# relay_matrix.net
KiCad netlist of a schematic drawn in Altium Designer
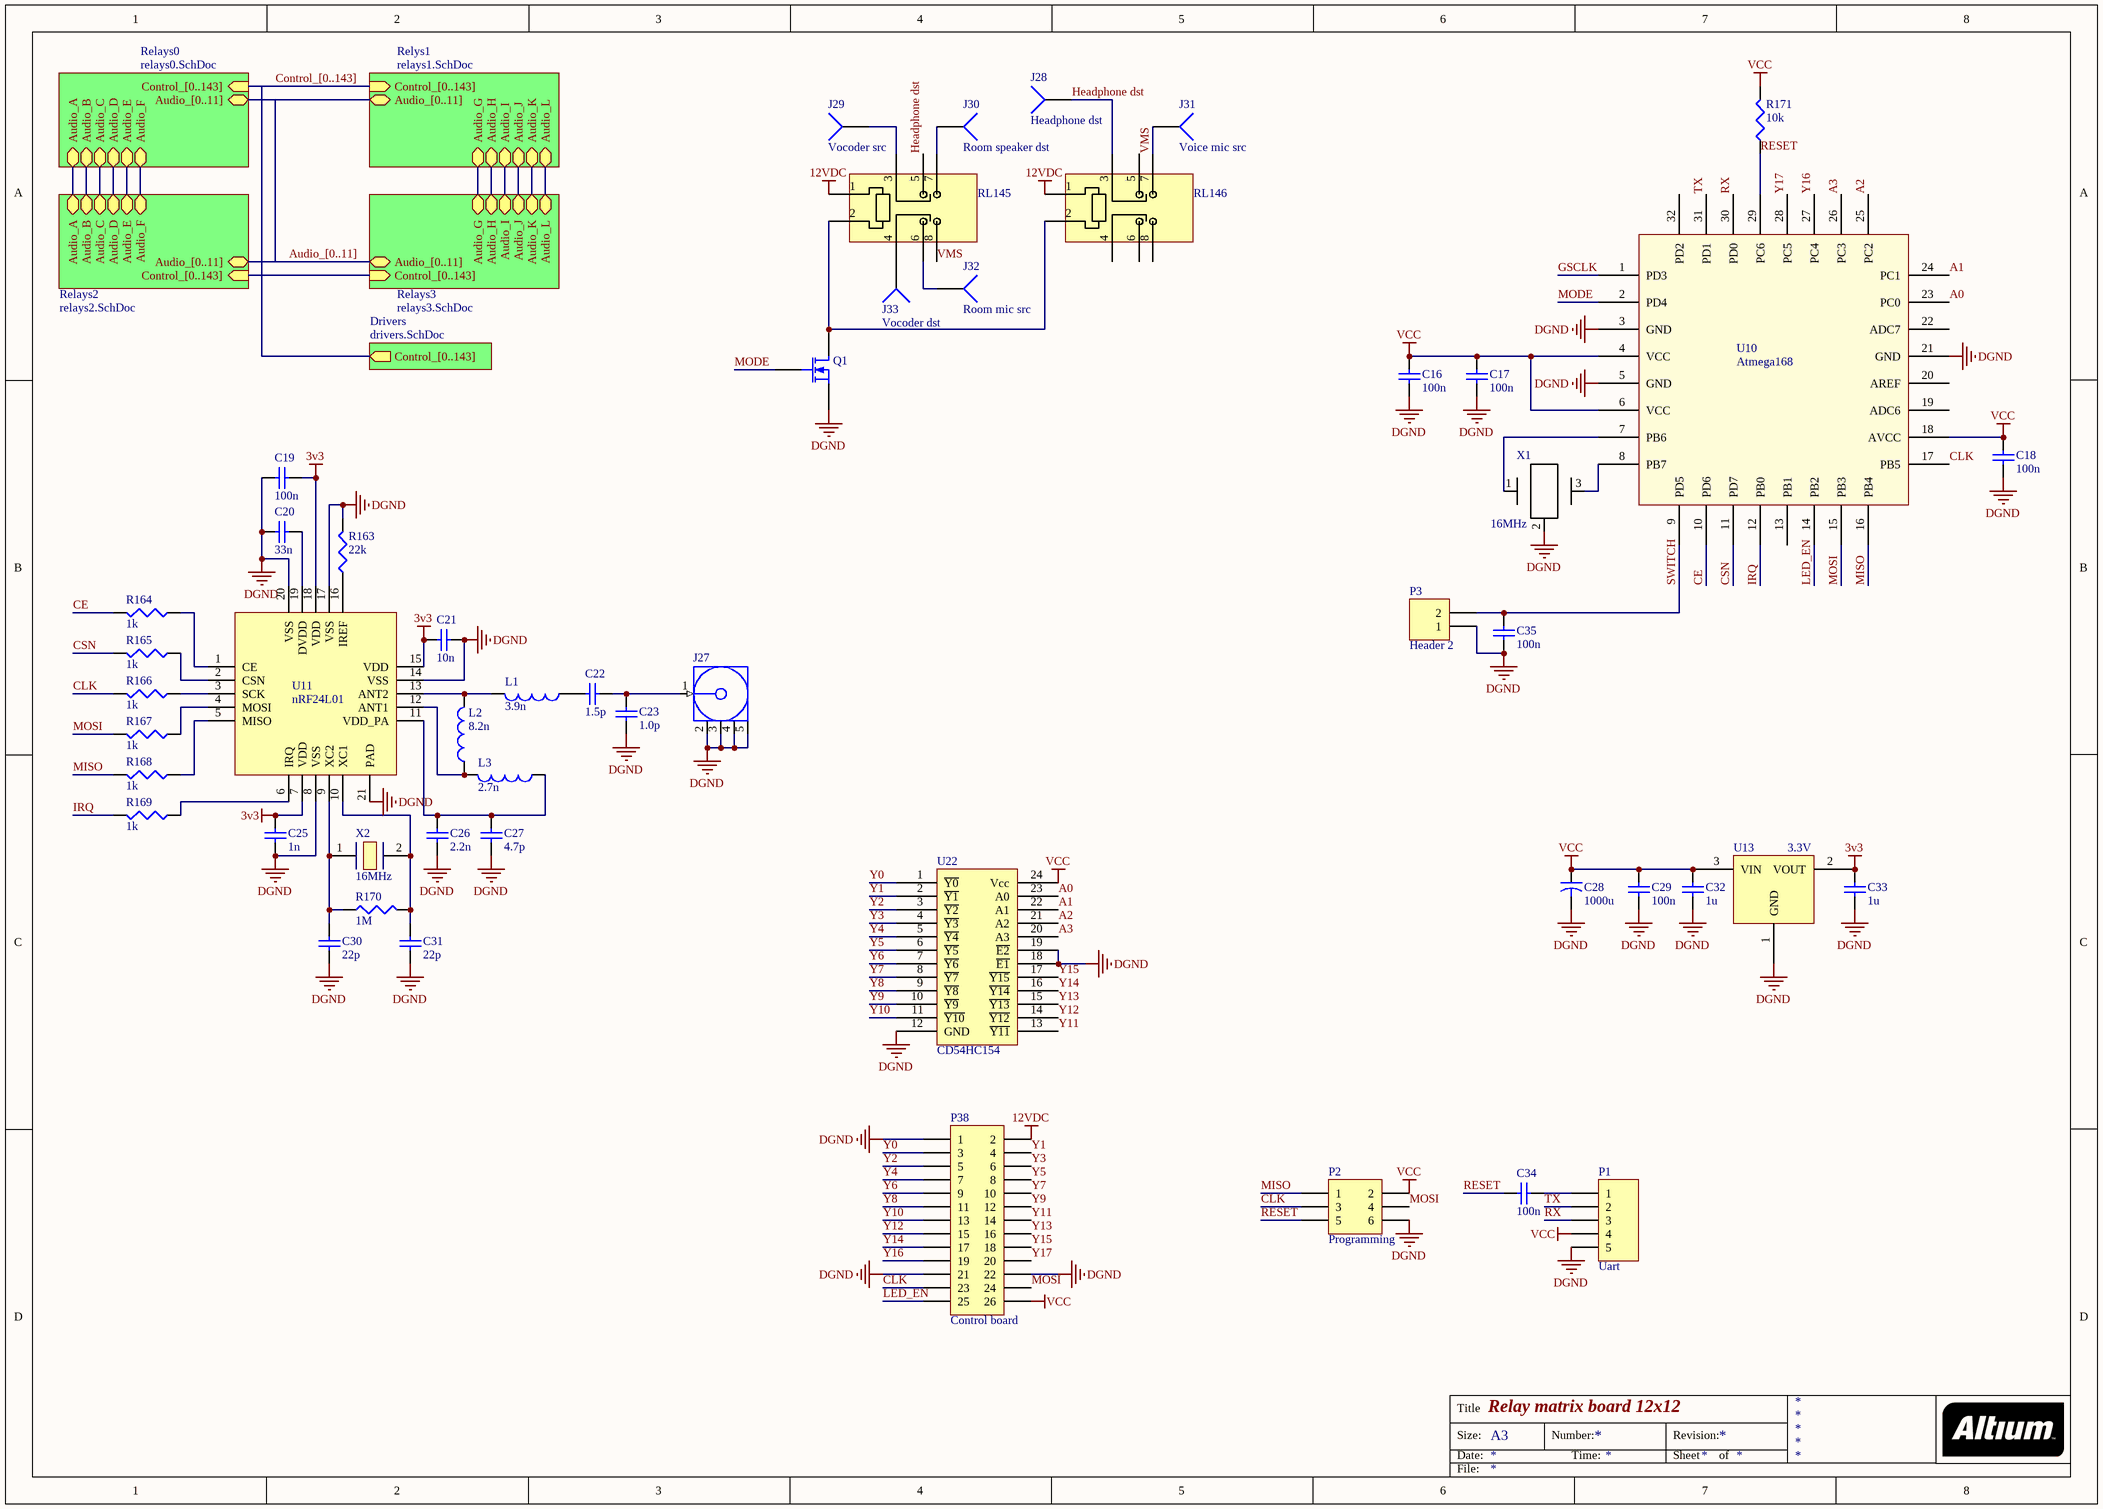
[diagram p0: relay_matrix.SchDoc]

(export (version "E")
  (design (tool "Eeschema 10.0.6"))
  (components
    (comp (ref "C16")
      (value "100n")
      (footprint "1608[0603]")
      (description "Capacitor (Semiconductor SIM Model)")
      (fields (field (name "Comment") "Cap Semi") (field (name "PUBLISHER") "Altium Limited"))
      (libsource (lib "Miscellaneous Devices") (part "Cap Semi"))
    )
    (comp (ref "C17")
      (value "100n")
      (footprint "1608[0603]")
      (description "Capacitor (Semiconductor SIM Model)")
      (fields (field (name "Comment") "Cap Semi") (field (name "PUBLISHER") "Altium Limited"))
      (libsource (lib "Miscellaneous Devices") (part "Cap Semi"))
    )
    (comp (ref "C18")
      (value "100n")
      (footprint "1608[0603]")
      (description "Capacitor (Semiconductor SIM Model)")
      (fields (field (name "Comment") "Cap Semi") (field (name "PUBLISHER") "Altium Limited"))
      (libsource (lib "Miscellaneous Devices") (part "Cap Semi"))
    )
    (comp (ref "C19")
      (value "100n")
      (footprint "1608[0603]")
      (description "Capacitor (Semiconductor SIM Model)")
      (fields (field (name "Comment") "Cap Semi") (field (name "PUBLISHER") "Altium Limited"))
      (libsource (lib "Miscellaneous Devices") (part "Cap Semi"))
    )
    (comp (ref "C20")
      (value "33n")
      (footprint "1608[0603]")
      (description "Capacitor (Semiconductor SIM Model)")
      (fields (field (name "Comment") "Cap Semi") (field (name "PUBLISHER") "Altium Limited"))
      (libsource (lib "Miscellaneous Devices") (part "Cap Semi"))
    )
    (comp (ref "C21")
      (value "10n")
      (footprint "1608[0603]")
      (description "Capacitor (Semiconductor SIM Model)")
      (fields (field (name "Comment") "Cap Semi") (field (name "PUBLISHER") "Altium Limited"))
      (libsource (lib "Miscellaneous Devices") (part "Cap Semi"))
    )
    (comp (ref "C22")
      (value "1.5p")
      (footprint "1608[0603]")
      (description "Capacitor (Semiconductor SIM Model)")
      (fields (field (name "Comment") "Cap Semi") (field (name "PUBLISHER") "Altium Limited"))
      (libsource (lib "Miscellaneous Devices") (part "Cap Semi"))
    )
    (comp (ref "C23")
      (value "1.0p")
      (footprint "1608[0603]")
      (description "Capacitor (Semiconductor SIM Model)")
      (fields (field (name "Comment") "Cap Semi") (field (name "PUBLISHER") "Altium Limited"))
      (libsource (lib "Miscellaneous Devices") (part "Cap Semi"))
    )
    (comp (ref "C25")
      (value "1n")
      (footprint "1608[0603]")
      (description "Capacitor (Semiconductor SIM Model)")
      (fields (field (name "Comment") "Cap Semi") (field (name "PUBLISHER") "Altium Limited"))
      (libsource (lib "Miscellaneous Devices") (part "Cap Semi"))
    )
    (comp (ref "C26")
      (value "2.2n")
      (footprint "1608[0603]")
      (description "Capacitor (Semiconductor SIM Model)")
      (fields (field (name "Comment") "Cap Semi") (field (name "PUBLISHER") "Altium Limited"))
      (libsource (lib "Miscellaneous Devices") (part "Cap Semi"))
    )
    (comp (ref "C27")
      (value "4.7p")
      (footprint "1608[0603]")
      (description "Capacitor (Semiconductor SIM Model)")
      (fields (field (name "Comment") "Cap Semi") (field (name "PUBLISHER") "Altium Limited"))
      (libsource (lib "Miscellaneous Devices") (part "Cap Semi"))
    )
    (comp (ref "C28")
      (value "1000u")
      (footprint "Cap_10x16mm")
      (description "Capacitor")
      (fields (field (name "Comment") "Cap2") (field (name "PUBLISHER") "Altium Limited"))
      (libsource (lib "Miscellaneous Devices") (part "Cap2"))
    )
    (comp (ref "C29")
      (value "100n")
      (footprint "1608[0603]")
      (description "Capacitor (Semiconductor SIM Model)")
      (fields (field (name "Comment") "Cap Semi") (field (name "PUBLISHER") "Altium Limited"))
      (libsource (lib "Miscellaneous Devices") (part "Cap Semi"))
    )
    (comp (ref "C30")
      (value "22p")
      (footprint "1608[0603]")
      (description "Capacitor (Semiconductor SIM Model)")
      (fields (field (name "Comment") "Cap Semi") (field (name "PUBLISHER") "Altium Limited"))
      (libsource (lib "Miscellaneous Devices") (part "Cap Semi"))
    )
    (comp (ref "C31")
      (value "22p")
      (footprint "1608[0603]")
      (description "Capacitor (Semiconductor SIM Model)")
      (fields (field (name "Comment") "Cap Semi") (field (name "PUBLISHER") "Altium Limited"))
      (libsource (lib "Miscellaneous Devices") (part "Cap Semi"))
    )
    (comp (ref "C32")
      (value "1u")
      (footprint "1608[0603]")
      (description "Capacitor (Semiconductor SIM Model)")
      (fields (field (name "Comment") "Cap Semi") (field (name "PUBLISHER") "Altium Limited"))
      (libsource (lib "Miscellaneous Devices") (part "Cap Semi"))
    )
    (comp (ref "C33")
      (value "1u")
      (footprint "1608[0603]")
      (description "Capacitor (Semiconductor SIM Model)")
      (fields (field (name "Comment") "Cap Semi") (field (name "PUBLISHER") "Altium Limited"))
      (libsource (lib "Miscellaneous Devices") (part "Cap Semi"))
    )
    (comp (ref "C34")
      (value "100n")
      (footprint "1608[0603]")
      (description "Capacitor (Semiconductor SIM Model)")
      (fields (field (name "Comment") "Cap Semi") (field (name "PUBLISHER") "Altium Limited"))
      (libsource (lib "Miscellaneous Devices") (part "Cap Semi"))
    )
    (comp (ref "C35")
      (value "100n")
      (footprint "1608[0603]")
      (description "Capacitor (Semiconductor SIM Model)")
      (fields (field (name "Comment") "Cap Semi") (field (name "PUBLISHER") "Altium Limited"))
      (libsource (lib "Miscellaneous Devices") (part "Cap Semi"))
    )
    (comp (ref "J27")
      (value "COAX-F")
      (footprint "MCX5.08-H5")
      (fields (field (name "PUBLISHER") "Altium Limited"))
      (libsource (lib "Miscellaneous Connectors") (part "COAX-F"))
    )
    (comp (ref "J28")
      (value "Headphone dst")
      (footprint "Conn_1_2x4")
      (description "Socket")
      (fields (field (name "PUBLISHER") "Altium Limited"))
      (libsource (lib "Miscellaneous Connectors") (part "Socket"))
    )
    (comp (ref "J29")
      (value "Vocoder src")
      (footprint "Conn_1_2x4")
      (description "Socket")
      (fields (field (name "PUBLISHER") "Altium Limited"))
      (libsource (lib "Miscellaneous Connectors") (part "Socket"))
    )
    (comp (ref "J30")
      (value "Room speaker dst")
      (footprint "Conn_1_2x4")
      (description "Socket")
      (fields (field (name "PUBLISHER") "Altium Limited"))
      (libsource (lib "Miscellaneous Connectors") (part "Socket"))
    )
    (comp (ref "J31")
      (value "Voice mic src")
      (footprint "Conn_1_2x4")
      (description "Socket")
      (fields (field (name "PUBLISHER") "Altium Limited"))
      (libsource (lib "Miscellaneous Connectors") (part "Socket"))
    )
    (comp (ref "J32")
      (value "Room mic src")
      (footprint "Conn_1_2x4")
      (description "Socket")
      (fields (field (name "PUBLISHER") "Altium Limited"))
      (libsource (lib "Miscellaneous Connectors") (part "Socket"))
    )
    (comp (ref "J33")
      (value "Vocoder dst")
      (footprint "Conn_1_2x4")
      (description "Socket")
      (fields (field (name "PUBLISHER") "Altium Limited"))
      (libsource (lib "Miscellaneous Connectors") (part "Socket"))
    )
    (comp (ref "L1")
      (value "3.9n")
      (footprint "1608[0603]")
      (description "Inductor")
      (fields (field (name "PUBLISHER") "Altium Limited"))
      (libsource (lib "Miscellaneous Devices") (part "Inductor"))
    )
    (comp (ref "L2")
      (value "8.2n")
      (footprint "1608[0603]")
      (description "Inductor")
      (fields (field (name "PUBLISHER") "Altium Limited"))
      (libsource (lib "Miscellaneous Devices") (part "Inductor"))
    )
    (comp (ref "L3")
      (value "2.7n")
      (footprint "1608[0603]")
      (description "Inductor")
      (fields (field (name "PUBLISHER") "Altium Limited"))
      (libsource (lib "Miscellaneous Devices") (part "Inductor"))
    )
    (comp (ref "P1")
      (value "Uart")
      (footprint "HDR1X5")
      (description "Header, 5-Pin")
      (fields (field (name "PUBLISHER") "Altium Limited"))
      (libsource (lib "Miscellaneous Connectors") (part "Header 5"))
    )
    (comp (ref "P2")
      (value "Programming")
      (footprint "HDR2X3H")
      (description "Header, 3-Pin, Dual row, Right Angle")
      (fields (field (name "PUBLISHER") "Altium Limited"))
      (libsource (lib "Miscellaneous Connectors") (part "Header 3X2H"))
    )
    (comp (ref "P3")
      (value "Header 2")
      (footprint "HDR1X2")
      (description "Header, 2-Pin")
      (fields (field (name "PUBLISHER") "Altium Limited"))
      (libsource (lib "Miscellaneous Connectors") (part "Header 2"))
    )
    (comp (ref "P38")
      (value "Control board")
      (footprint "HDR2X13")
      (description "Header, 13-Pin, Dual row")
      (fields (field (name "PUBLISHER") "Altium Limited"))
      (libsource (lib "Miscellaneous Connectors") (part "Header 13X2"))
    )
    (comp (ref "Q1")
      (value "MOSFET-N")
      (footprint "SOT23_M")
      (description "N-Channel MOSFET")
      (fields (field (name "PUBLISHER") "Altium Limited"))
      (libsource (lib "Miscellaneous Devices") (part "MOSFET-N"))
    )
    (comp (ref "R163")
      (value "22k")
      (footprint "J1-0603")
      (description "Resistor")
      (fields (field (name "Comment") "Res3") (field (name "PUBLISHER") "Altium Limited"))
      (libsource (lib "Miscellaneous Devices") (part "Res3"))
    )
    (comp (ref "R164")
      (value "1k")
      (footprint "J1-0603")
      (description "Resistor")
      (fields (field (name "Comment") "Res3") (field (name "PUBLISHER") "Altium Limited"))
      (libsource (lib "Miscellaneous Devices") (part "Res3"))
    )
    (comp (ref "R165")
      (value "1k")
      (footprint "J1-0603")
      (description "Resistor")
      (fields (field (name "Comment") "Res3") (field (name "PUBLISHER") "Altium Limited"))
      (libsource (lib "Miscellaneous Devices") (part "Res3"))
    )
    (comp (ref "R166")
      (value "1k")
      (footprint "J1-0603")
      (description "Resistor")
      (fields (field (name "Comment") "Res3") (field (name "PUBLISHER") "Altium Limited"))
      (libsource (lib "Miscellaneous Devices") (part "Res3"))
    )
    (comp (ref "R167")
      (value "1k")
      (footprint "J1-0603")
      (description "Resistor")
      (fields (field (name "Comment") "Res3") (field (name "PUBLISHER") "Altium Limited"))
      (libsource (lib "Miscellaneous Devices") (part "Res3"))
    )
    (comp (ref "R168")
      (value "1k")
      (footprint "J1-0603")
      (description "Resistor")
      (fields (field (name "Comment") "Res3") (field (name "PUBLISHER") "Altium Limited"))
      (libsource (lib "Miscellaneous Devices") (part "Res3"))
    )
    (comp (ref "R169")
      (value "1k")
      (footprint "J1-0603")
      (description "Resistor")
      (fields (field (name "Comment") "Res3") (field (name "PUBLISHER") "Altium Limited"))
      (libsource (lib "Miscellaneous Devices") (part "Res3"))
    )
    (comp (ref "R170")
      (value "1M")
      (footprint "J1-0603")
      (description "Resistor")
      (fields (field (name "Comment") "Res3") (field (name "PUBLISHER") "Altium Limited"))
      (libsource (lib "Miscellaneous Devices") (part "Res3"))
    )
    (comp (ref "R171")
      (value "10k")
      (footprint "J1-0603")
      (description "Resistor")
      (fields (field (name "Comment") "Res3") (field (name "PUBLISHER") "Altium Limited"))
      (libsource (lib "Miscellaneous Devices") (part "Res3"))
    )
    (comp (ref "RL145")
      (value "Relay")
      (footprint "Relay_S13")
      (description "Miniature power relay")
      (fields (field (name "PART NUMBER") "S13-12V-2C"))
      (libsource (lib "tech-thing") (part "Relay_S13"))
    )
    (comp (ref "RL146")
      (value "Relay")
      (footprint "Relay_S13")
      (description "Miniature power relay")
      (fields (field (name "PART NUMBER") "S13-12V-2C"))
      (libsource (lib "tech-thing") (part "Relay_S13"))
    )
    (comp (ref "U10")
      (value "Atmega168")
      (footprint "TQFP-32")
      (libsource (lib "tech-thing") (part "Atmega168"))
    )
    (comp (ref "U11")
      (value "nRF24L01")
      (footprint "QFN20")
      (description "Single Chip 2.4GHz Transciever")
      (libsource (lib "tech-thing") (part "nRF24L01"))
    )
    (comp (ref "U13")
      (value "3.3V")
      (footprint "SOT23")
      (description "Fixed voltage regulator")
      (fields (field (name "PART NUMBER") "2363085"))
      (libsource (lib "tech-thing") (part "Voltage_regulator_3pin"))
    )
    (comp (ref "U22")
      (value "CD54HC154")
      (footprint "SO24")
      (description "High speed logic 4 to 16 decoder")
      (fields (field (name "PART NUMBER") "2407121"))
      (libsource (lib "tech-thing") (part "CD54HC154"))
    )
    (comp (ref "X1")
      (value "16MHz")
      (footprint "SMD-RESONATOR")
      (fields (field (name "Comment") "Resonator"))
      (libsource (lib "tech-thing") (part "Resonator"))
    )
    (comp (ref "X2")
      (value "16MHz")
      (footprint "Crystal_7A_series")
      (fields (field (name "Comment") "Crystal"))
      (libsource (lib "tech-thing") (part "Crystal"))
    )
  )
  (nets
    (net (code "157") (name "/A0") (class "Default")
      (node (ref "U10") (pin "23") (pinfunction "PC0_23") (pintype "passive"))
      (node (ref "U22") (pin "23") (pinfunction "A0_23") (pintype "passive"))
    )
    (net (code "158") (name "/A1") (class "Default")
      (node (ref "U10") (pin "24") (pinfunction "PC1_24") (pintype "passive"))
      (node (ref "U22") (pin "22") (pinfunction "A1_22") (pintype "passive"))
    )
    (net (code "159") (name "/A2") (class "Default")
      (node (ref "U10") (pin "25") (pinfunction "PC2_25") (pintype "passive"))
      (node (ref "U22") (pin "21") (pinfunction "A2_21") (pintype "passive"))
    )
    (net (code "160") (name "/A3") (class "Default")
      (node (ref "U10") (pin "26") (pinfunction "PC3_26") (pintype "passive"))
      (node (ref "U22") (pin "20") (pinfunction "A3_20") (pintype "passive"))
    )
    (net (code "175") (name "/CE") (class "Default")
      (node (ref "R164") (pin "2") (pinfunction "2_2") (pintype "passive"))
      (node (ref "U10") (pin "10") (pinfunction "PD6_10") (pintype "passive"))
    )
    (net (code "176") (name "/CLK") (class "Default")
      (node (ref "P2") (pin "3") (pinfunction "3_3") (pintype "passive"))
      (node (ref "P38") (pin "23") (pinfunction "23_23") (pintype "passive"))
      (node (ref "R166") (pin "2") (pinfunction "2_2") (pintype "passive"))
      (node (ref "U10") (pin "17") (pinfunction "PB5_17") (pintype "passive"))
    )
    (net (code "177") (name "/CSN") (class "Default")
      (node (ref "R165") (pin "2") (pinfunction "2_2") (pintype "passive"))
      (node (ref "U10") (pin "11") (pinfunction "PD7_11") (pintype "passive"))
    )
    (net (code "181") (name "/GSCLK") (class "Default")
      (node (ref "U10") (pin "1") (pinfunction "PD3_1") (pintype "passive"))
    )
    (net (code "182") (name "/Headphone dst") (class "Default")
      (node (ref "J28") (pin "1") (pinfunction "1_1") (pintype "passive"))
      (node (ref "RL145") (pin "5") (pintype "passive"))
      (node (ref "RL146") (pin "3") (pintype "passive"))
    )
    (net (code "183") (name "/IRQ") (class "Default")
      (node (ref "R169") (pin "2") (pinfunction "2_2") (pintype "passive"))
      (node (ref "U10") (pin "12") (pinfunction "PB0_12") (pintype "passive"))
    )
    (net (code "184") (name "/LED_EN") (class "Default")
      (node (ref "P38") (pin "25") (pinfunction "25_25") (pintype "passive"))
      (node (ref "U10") (pin "14") (pinfunction "PB2_14") (pintype "passive"))
    )
    (net (code "185") (name "/MISO") (class "Default")
      (node (ref "P2") (pin "1") (pinfunction "1_1") (pintype "passive"))
      (node (ref "R168") (pin "2") (pinfunction "2_2") (pintype "passive"))
      (node (ref "U10") (pin "16") (pinfunction "PB4_16") (pintype "passive"))
    )
    (net (code "186") (name "/MODE") (class "Default")
      (node (ref "Q1") (pin "2") (pinfunction "G_2") (pintype "passive"))
      (node (ref "U10") (pin "2") (pinfunction "PD4_2") (pintype "passive"))
    )
    (net (code "187") (name "/MOSI") (class "Default")
      (node (ref "P2") (pin "4") (pinfunction "4_4") (pintype "passive"))
      (node (ref "P38") (pin "24") (pinfunction "24_24") (pintype "passive"))
      (node (ref "R167") (pin "2") (pinfunction "2_2") (pintype "passive"))
      (node (ref "U10") (pin "15") (pinfunction "PB3_15") (pintype "passive"))
    )
    (net (code "188") (name "/RESET") (class "Default")
      (node (ref "C34") (pin "1") (pinfunction "1_1") (pintype "passive"))
      (node (ref "P2") (pin "5") (pinfunction "5_5") (pintype "passive"))
      (node (ref "R171") (pin "1") (pinfunction "1_1") (pintype "passive"))
      (node (ref "U10") (pin "29") (pinfunction "PC6_29") (pintype "passive"))
    )
    (net (code "189") (name "/RX") (class "Default")
      (node (ref "P1") (pin "3") (pinfunction "3_3") (pintype "passive"))
      (node (ref "U10") (pin "30") (pinfunction "PD0_30") (pintype "passive"))
    )
    (net (code "190") (name "/SWITCH") (class "Default")
      (node (ref "C35") (pin "1") (pinfunction "1_1") (pintype "passive"))
      (node (ref "P3") (pin "2") (pinfunction "2_2") (pintype "passive"))
      (node (ref "U10") (pin "9") (pinfunction "PD5_9") (pintype "passive"))
    )
    (net (code "191") (name "/TX") (class "Default")
      (node (ref "P1") (pin "2") (pinfunction "2_2") (pintype "passive"))
      (node (ref "U10") (pin "31") (pinfunction "PD1_31") (pintype "passive"))
    )
    (net (code "192") (name "/VMS") (class "Default")
      (node (ref "J31") (pin "1") (pinfunction "1_1") (pintype "passive"))
      (node (ref "RL145") (pin "8") (pinfunction "8_8") (pintype "passive"))
      (node (ref "RL146") (pin "7") (pintype "passive"))
    )
    (net (code "193") (name "/Y0") (class "Default")
      (node (ref "P38") (pin "3") (pinfunction "3_3") (pintype "passive"))
      (node (ref "U22") (pin "1") (pinfunction "~{Y0}_1") (pintype "passive"))
    )
    (net (code "194") (name "/Y1") (class "Default")
      (node (ref "P38") (pin "4") (pinfunction "4_4") (pintype "passive"))
      (node (ref "U22") (pin "2") (pinfunction "~{Y1}_2") (pintype "passive"))
    )
    (net (code "195") (name "/Y2") (class "Default")
      (node (ref "P38") (pin "5") (pinfunction "5_5") (pintype "passive"))
      (node (ref "U22") (pin "3") (pinfunction "~{Y2}_3") (pintype "passive"))
    )
    (net (code "196") (name "/Y3") (class "Default")
      (node (ref "P38") (pin "6") (pinfunction "6_6") (pintype "passive"))
      (node (ref "U22") (pin "4") (pinfunction "~{Y3}_4") (pintype "passive"))
    )
    (net (code "197") (name "/Y4") (class "Default")
      (node (ref "P38") (pin "7") (pinfunction "7_7") (pintype "passive"))
      (node (ref "U22") (pin "5") (pinfunction "~{Y4}_5") (pintype "passive"))
    )
    (net (code "198") (name "/Y5") (class "Default")
      (node (ref "P38") (pin "8") (pinfunction "8_8") (pintype "passive"))
      (node (ref "U22") (pin "6") (pinfunction "~{Y5}_6") (pintype "passive"))
    )
    (net (code "199") (name "/Y6") (class "Default")
      (node (ref "P38") (pin "9") (pinfunction "9_9") (pintype "passive"))
      (node (ref "U22") (pin "7") (pinfunction "~{Y6}_7") (pintype "passive"))
    )
    (net (code "200") (name "/Y7") (class "Default")
      (node (ref "P38") (pin "10") (pinfunction "10_10") (pintype "passive"))
      (node (ref "U22") (pin "8") (pinfunction "~{Y7}_8") (pintype "passive"))
    )
    (net (code "201") (name "/Y8") (class "Default")
      (node (ref "P38") (pin "11") (pinfunction "11_11") (pintype "passive"))
      (node (ref "U22") (pin "9") (pinfunction "~{Y8}_9") (pintype "passive"))
    )
    (net (code "202") (name "/Y9") (class "Default")
      (node (ref "P38") (pin "12") (pinfunction "12_12") (pintype "passive"))
      (node (ref "U22") (pin "10") (pinfunction "~{Y9}_10") (pintype "passive"))
    )
    (net (code "203") (name "/Y10") (class "Default")
      (node (ref "P38") (pin "13") (pinfunction "13_13") (pintype "passive"))
      (node (ref "U22") (pin "11") (pinfunction "~{Y10}_11") (pintype "passive"))
    )
    (net (code "204") (name "/Y11") (class "Default")
      (node (ref "P38") (pin "14") (pinfunction "14_14") (pintype "passive"))
      (node (ref "U22") (pin "13") (pinfunction "~{Y11}_13") (pintype "passive"))
    )
    (net (code "205") (name "/Y12") (class "Default")
      (node (ref "P38") (pin "15") (pinfunction "15_15") (pintype "passive"))
      (node (ref "U22") (pin "14") (pinfunction "~{Y12}_14") (pintype "passive"))
    )
    (net (code "206") (name "/Y13") (class "Default")
      (node (ref "P38") (pin "16") (pinfunction "16_16") (pintype "passive"))
      (node (ref "U22") (pin "15") (pinfunction "~{Y13}_15") (pintype "passive"))
    )
    (net (code "207") (name "/Y14") (class "Default")
      (node (ref "P38") (pin "17") (pinfunction "17_17") (pintype "passive"))
      (node (ref "U22") (pin "16") (pinfunction "~{Y14}_16") (pintype "passive"))
    )
    (net (code "208") (name "/Y15") (class "Default")
      (node (ref "P38") (pin "18") (pinfunction "18_18") (pintype "passive"))
      (node (ref "U22") (pin "17") (pinfunction "~{Y15}_17") (pintype "passive"))
    )
    (net (code "209") (name "/Y16") (class "Default")
      (node (ref "P38") (pin "19") (pinfunction "19_19") (pintype "passive"))
      (node (ref "U10") (pin "27") (pinfunction "PC4_27") (pintype "passive"))
    )
    (net (code "210") (name "/Y17") (class "Default")
      (node (ref "P38") (pin "20") (pinfunction "20_20") (pintype "passive"))
      (node (ref "U10") (pin "28") (pinfunction "PC5_28") (pintype "passive"))
    )
    (net (code "211") (name "3v3") (class "Default")
      (node (ref "C19") (pin "2") (pinfunction "2_2") (pintype "passive"))
      (node (ref "C21") (pin "1") (pinfunction "1_1") (pintype "passive"))
      (node (ref "C25") (pin "1") (pinfunction "1_1") (pintype "passive"))
      (node (ref "C33") (pin "1") (pinfunction "1_1") (pintype "passive"))
      (node (ref "U11") (pin "15") (pinfunction "VDD_15") (pintype "passive"))
      (node (ref "U11") (pin "18") (pinfunction "VDD_18") (pintype "passive"))
      (node (ref "U11") (pin "7") (pinfunction "VDD_7") (pintype "passive"))
      (node (ref "U13") (pin "2") (pinfunction "VOUT_2") (pintype "passive"))
    )
    (net (code "212") (name "12VDC") (class "Default")
      (node (ref "P38") (pin "2") (pinfunction "2_2") (pintype "passive"))
      (node (ref "RL145") (pin "1") (pintype "passive"))
      (node (ref "RL146") (pin "1") (pintype "passive"))
    )
    (net (code "213") (name "DGND") (class "Default")
      (node (ref "C16") (pin "2") (pinfunction "2_2") (pintype "passive"))
      (node (ref "C17") (pin "2") (pinfunction "2_2") (pintype "passive"))
      (node (ref "C18") (pin "2") (pinfunction "2_2") (pintype "passive"))
      (node (ref "C19") (pin "1") (pinfunction "1_1") (pintype "passive"))
      (node (ref "C20") (pin "1") (pinfunction "1_1") (pintype "passive"))
      (node (ref "C21") (pin "2") (pinfunction "2_2") (pintype "passive"))
      (node (ref "C23") (pin "2") (pinfunction "2_2") (pintype "passive"))
      (node (ref "C25") (pin "2") (pinfunction "2_2") (pintype "passive"))
      (node (ref "C26") (pin "2") (pinfunction "2_2") (pintype "passive"))
      (node (ref "C27") (pin "2") (pinfunction "2_2") (pintype "passive"))
      (node (ref "C28") (pin "2") (pinfunction "2_2") (pintype "passive"))
      (node (ref "C29") (pin "2") (pinfunction "2_2") (pintype "passive"))
      (node (ref "C30") (pin "2") (pinfunction "2_2") (pintype "passive"))
      (node (ref "C31") (pin "2") (pinfunction "2_2") (pintype "passive"))
      (node (ref "C32") (pin "2") (pinfunction "2_2") (pintype "passive"))
      (node (ref "C33") (pin "2") (pinfunction "2_2") (pintype "passive"))
      (node (ref "C35") (pin "2") (pinfunction "2_2") (pintype "passive"))
      (node (ref "J27") (pin "2") (pinfunction "GND_2") (pintype "power_in"))
      (node (ref "J27") (pin "3") (pinfunction "GND_3") (pintype "power_in"))
      (node (ref "J27") (pin "4") (pinfunction "GND_4") (pintype "power_in"))
      (node (ref "J27") (pin "5") (pinfunction "GND_5") (pintype "power_in"))
      (node (ref "P1") (pin "5") (pinfunction "5_5") (pintype "passive"))
      (node (ref "P2") (pin "6") (pinfunction "6_6") (pintype "passive"))
      (node (ref "P3") (pin "1") (pinfunction "1_1") (pintype "passive"))
      (node (ref "P38") (pin "1") (pinfunction "1_1") (pintype "passive"))
      (node (ref "P38") (pin "21") (pinfunction "21_21") (pintype "passive"))
      (node (ref "P38") (pin "22") (pinfunction "22_22") (pintype "passive"))
      (node (ref "Q1") (pin "3") (pinfunction "S_3") (pintype "passive"))
      (node (ref "R163") (pin "2") (pinfunction "2_2") (pintype "passive"))
      (node (ref "U10") (pin "21") (pinfunction "GND_21") (pintype "passive"))
      (node (ref "U10") (pin "3") (pinfunction "GND_3") (pintype "passive"))
      (node (ref "U10") (pin "5") (pinfunction "GND_5") (pintype "passive"))
      (node (ref "U11") (pin "14") (pinfunction "VSS_14") (pintype "passive"))
      (node (ref "U11") (pin "17") (pinfunction "VSS_17") (pintype "passive"))
      (node (ref "U11") (pin "20") (pinfunction "VSS_20") (pintype "passive"))
      (node (ref "U11") (pin "21") (pinfunction "PAD_21") (pintype "passive"))
      (node (ref "U11") (pin "8") (pinfunction "VSS_8") (pintype "passive"))
      (node (ref "U13") (pin "1") (pinfunction "GND_1") (pintype "passive"))
      (node (ref "U22") (pin "12") (pinfunction "GND_12") (pintype "passive"))
      (node (ref "U22") (pin "18") (pinfunction "~{E1}_18") (pintype "passive"))
      (node (ref "U22") (pin "19") (pinfunction "~{E2}_19") (pintype "passive"))
      (node (ref "X1") (pin "2") (pinfunction "12_2") (pintype "passive"))
    )
    (net (code "214") (name "Net-(C22-Pad1)") (class "Default")
      (node (ref "C22") (pin "1") (pinfunction "1_1") (pintype "passive"))
      (node (ref "L1") (pin "1") (pinfunction "1_1") (pintype "passive"))
    )
    (net (code "215") (name "Net-(C34-Pad2)") (class "Default")
      (node (ref "C34") (pin "2") (pinfunction "2_2") (pintype "passive"))
      (node (ref "P1") (pin "1") (pinfunction "1_1") (pintype "passive"))
    )
    (net (code "216") (name "Net-(J27-Signal)") (class "Default")
      (node (ref "C22") (pin "2") (pinfunction "2_2") (pintype "passive"))
      (node (ref "C23") (pin "1") (pinfunction "1_1") (pintype "passive"))
      (node (ref "J27") (pin "1") (pinfunction "Signal_1") (pintype "input"))
    )
    (net (code "217") (name "Net-(J29-Pad1)") (class "Default")
      (node (ref "J29") (pin "1") (pinfunction "1_1") (pintype "passive"))
      (node (ref "RL145") (pin "3") (pintype "passive"))
    )
    (net (code "218") (name "Net-(J30-Pad1)") (class "Default")
      (node (ref "J30") (pin "1") (pinfunction "1_1") (pintype "passive"))
      (node (ref "RL145") (pin "7") (pintype "passive"))
    )
    (net (code "219") (name "Net-(J32-Pad1)") (class "Default")
      (node (ref "J32") (pin "1") (pinfunction "1_1") (pintype "passive"))
      (node (ref "RL145") (pin "6") (pintype "passive"))
    )
    (net (code "220") (name "Net-(J33-Pad1)") (class "Default")
      (node (ref "J33") (pin "1") (pinfunction "1_1") (pintype "passive"))
      (node (ref "RL145") (pin "4") (pintype "passive"))
    )
    (net (code "221") (name "Net-(Q1-D)") (class "Default")
      (node (ref "Q1") (pin "1") (pinfunction "D_1") (pintype "passive"))
      (node (ref "RL145") (pin "2") (pintype "passive"))
      (node (ref "RL146") (pin "2") (pintype "passive"))
    )
    (net (code "222") (name "Net-(U10-PB6)") (class "Default")
      (node (ref "U10") (pin "7") (pinfunction "PB6_7") (pintype "passive"))
      (node (ref "X1") (pin "1") (pinfunction "11_1") (pintype "passive"))
    )
    (net (code "223") (name "Net-(U10-PB7)") (class "Default")
      (node (ref "U10") (pin "8") (pinfunction "PB7_8") (pintype "passive"))
      (node (ref "X1") (pin "3") (pinfunction "13_3") (pintype "passive"))
    )
    (net (code "224") (name "Net-(U11-ANT1)") (class "Default")
      (node (ref "L2") (pin "1") (pinfunction "1_1") (pintype "passive"))
      (node (ref "L3") (pin "2") (pinfunction "2_2") (pintype "passive"))
      (node (ref "U11") (pin "12") (pinfunction "ANT1_12") (pintype "passive"))
    )
    (net (code "225") (name "Net-(U11-ANT2)") (class "Default")
      (node (ref "L1") (pin "2") (pinfunction "2_2") (pintype "passive"))
      (node (ref "L2") (pin "2") (pinfunction "2_2") (pintype "passive"))
      (node (ref "U11") (pin "13") (pinfunction "ANT2_13") (pintype "passive"))
    )
    (net (code "226") (name "Net-(U11-CE)") (class "Default")
      (node (ref "R164") (pin "1") (pinfunction "1_1") (pintype "passive"))
      (node (ref "U11") (pin "1") (pinfunction "CE_1") (pintype "passive"))
    )
    (net (code "227") (name "Net-(U11-CSN)") (class "Default")
      (node (ref "R165") (pin "1") (pinfunction "1_1") (pintype "passive"))
      (node (ref "U11") (pin "2") (pinfunction "CSN_2") (pintype "passive"))
    )
    (net (code "228") (name "Net-(U11-DVDD)") (class "Default")
      (node (ref "C20") (pin "2") (pinfunction "2_2") (pintype "passive"))
      (node (ref "U11") (pin "19") (pinfunction "DVDD_19") (pintype "passive"))
    )
    (net (code "229") (name "Net-(U11-IREF)") (class "Default")
      (node (ref "R163") (pin "1") (pinfunction "1_1") (pintype "passive"))
      (node (ref "U11") (pin "16") (pinfunction "IREF_16") (pintype "passive"))
    )
    (net (code "230") (name "Net-(U11-IRQ)") (class "Default")
      (node (ref "R169") (pin "1") (pinfunction "1_1") (pintype "passive"))
      (node (ref "U11") (pin "6") (pinfunction "IRQ_6") (pintype "passive"))
    )
    (net (code "231") (name "Net-(U11-MISO)") (class "Default")
      (node (ref "R168") (pin "1") (pinfunction "1_1") (pintype "passive"))
      (node (ref "U11") (pin "5") (pinfunction "MISO_5") (pintype "passive"))
    )
    (net (code "232") (name "Net-(U11-MOSI)") (class "Default")
      (node (ref "R167") (pin "1") (pinfunction "1_1") (pintype "passive"))
      (node (ref "U11") (pin "4") (pinfunction "MOSI_4") (pintype "passive"))
    )
    (net (code "233") (name "Net-(U11-SCK)") (class "Default")
      (node (ref "R166") (pin "1") (pinfunction "1_1") (pintype "passive"))
      (node (ref "U11") (pin "3") (pinfunction "SCK_3") (pintype "passive"))
    )
    (net (code "234") (name "Net-(U11-VDD_PA)") (class "Default")
      (node (ref "C26") (pin "1") (pinfunction "1_1") (pintype "passive"))
      (node (ref "C27") (pin "1") (pinfunction "1_1") (pintype "passive"))
      (node (ref "L3") (pin "1") (pinfunction "1_1") (pintype "passive"))
      (node (ref "U11") (pin "11") (pinfunction "VDD_PA_11") (pintype "passive"))
    )
    (net (code "235") (name "Net-(U11-XC1)") (class "Default")
      (node (ref "C31") (pin "1") (pinfunction "1_1") (pintype "passive"))
      (node (ref "R170") (pin "2") (pinfunction "2_2") (pintype "passive"))
      (node (ref "U11") (pin "10") (pinfunction "XC1_10") (pintype "passive"))
      (node (ref "X2") (pin "2") (pintype "passive"))
    )
    (net (code "236") (name "Net-(U11-XC2)") (class "Default")
      (node (ref "C30") (pin "1") (pinfunction "1_1") (pintype "passive"))
      (node (ref "R170") (pin "1") (pinfunction "1_1") (pintype "passive"))
      (node (ref "U11") (pin "9") (pinfunction "XC2_9") (pintype "passive"))
      (node (ref "X2") (pin "1") (pintype "passive"))
    )
    (net (code "237") (name "VCC") (class "Default")
      (node (ref "C16") (pin "1") (pinfunction "1_1") (pintype "passive"))
      (node (ref "C17") (pin "1") (pinfunction "1_1") (pintype "passive"))
      (node (ref "C18") (pin "1") (pinfunction "1_1") (pintype "passive"))
      (node (ref "C28") (pin "1") (pinfunction "1_1") (pintype "passive"))
      (node (ref "C29") (pin "1") (pinfunction "1_1") (pintype "passive"))
      (node (ref "C32") (pin "1") (pinfunction "1_1") (pintype "passive"))
      (node (ref "P1") (pin "4") (pinfunction "4_4") (pintype "passive"))
      (node (ref "P2") (pin "2") (pinfunction "2_2") (pintype "passive"))
      (node (ref "P38") (pin "26") (pinfunction "26_26") (pintype "passive"))
      (node (ref "R171") (pin "2") (pinfunction "2_2") (pintype "passive"))
      (node (ref "U10") (pin "18") (pinfunction "AVCC_18") (pintype "passive"))
      (node (ref "U10") (pin "4") (pinfunction "VCC_4") (pintype "passive"))
      (node (ref "U10") (pin "6") (pinfunction "VCC_6") (pintype "passive"))
      (node (ref "U13") (pin "3") (pinfunction "VIN_3") (pintype "passive"))
      (node (ref "U22") (pin "24") (pinfunction "Vcc_24") (pintype "passive"))
    )
    (net (code "238") (name "unconnected-(RL146-Pad4)") (class "Default")
      (node (ref "RL146") (pin "4") (pintype "passive"))
    )
    (net (code "239") (name "unconnected-(RL146-Pad5)") (class "Default")
      (node (ref "RL146") (pin "5") (pintype "passive"))
    )
    (net (code "240") (name "unconnected-(RL146-Pad6)") (class "Default")
      (node (ref "RL146") (pin "6") (pintype "passive"))
    )
    (net (code "241") (name "unconnected-(RL146-Pad8)") (class "Default")
      (node (ref "RL146") (pin "8") (pinfunction "8_8") (pintype "passive"))
    )
    (net (code "242") (name "unconnected-(U10-ADC6-Pad19)") (class "Default")
      (node (ref "U10") (pin "19") (pinfunction "ADC6_19") (pintype "passive"))
    )
    (net (code "243") (name "unconnected-(U10-ADC7-Pad22)") (class "Default")
      (node (ref "U10") (pin "22") (pinfunction "ADC7_22") (pintype "passive"))
    )
    (net (code "244") (name "unconnected-(U10-AREF-Pad20)") (class "Default")
      (node (ref "U10") (pin "20") (pinfunction "AREF_20") (pintype "passive"))
    )
    (net (code "245") (name "unconnected-(U10-PB1-Pad13)") (class "Default")
      (node (ref "U10") (pin "13") (pinfunction "PB1_13") (pintype "passive"))
    )
    (net (code "246") (name "unconnected-(U10-PD2-Pad32)") (class "Default")
      (node (ref "U10") (pin "32") (pinfunction "PD2_32") (pintype "passive"))
    )
  )
)
